# 7688A-kit-V2-2.net
KiCad netlist of a schematic drawn in Altium Designer
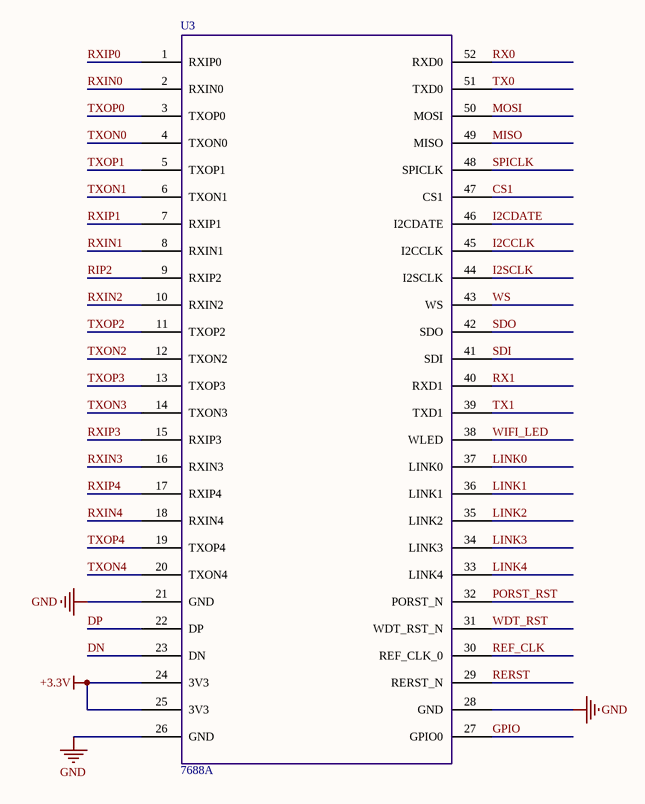
[diagram p0: 7688A-kit-V2-2.SchDoc]

(export (version "E")
  (design (tool "Eeschema 10.0.6"))
  (components
    (comp (ref "U3")
      (value "7688A")
      (footprint "7688A:RM08K_52pin")
      (libsource (lib "7688A") (part "Component_1"))
    )
  )
  (nets
    (net (code "1") (name "+3.3V") (class "Default")
      (node (ref "U3") (pin "24") (pinfunction "3V3_24") (pintype "passive"))
      (node (ref "U3") (pin "25") (pinfunction "3V3_25") (pintype "passive"))
    )
    (net (code "2") (name "/CS1") (class "Default")
      (node (ref "U3") (pin "47") (pinfunction "CS1_47") (pintype "passive"))
    )
    (net (code "3") (name "/DN") (class "Default")
      (node (ref "U3") (pin "23") (pinfunction "DN_23") (pintype "passive"))
    )
    (net (code "4") (name "/DP") (class "Default")
      (node (ref "U3") (pin "22") (pinfunction "DP_22") (pintype "passive"))
    )
    (net (code "5") (name "/GPIO") (class "Default")
      (node (ref "U3") (pin "27") (pinfunction "GPIO0_27") (pintype "passive"))
    )
    (net (code "6") (name "/I2CCLK") (class "Default")
      (node (ref "U3") (pin "45") (pinfunction "I2CCLK_45") (pintype "passive"))
    )
    (net (code "7") (name "/I2CDATE") (class "Default")
      (node (ref "U3") (pin "46") (pinfunction "I2CDATE_46") (pintype "passive"))
    )
    (net (code "8") (name "/I2SCLK") (class "Default")
      (node (ref "U3") (pin "44") (pinfunction "I2SCLK_44") (pintype "passive"))
    )
    (net (code "9") (name "/LINK0") (class "Default")
      (node (ref "U3") (pin "37") (pinfunction "LINK0_37") (pintype "passive"))
    )
    (net (code "10") (name "/LINK1") (class "Default")
      (node (ref "U3") (pin "36") (pinfunction "LINK1_36") (pintype "passive"))
    )
    (net (code "11") (name "/LINK2") (class "Default")
      (node (ref "U3") (pin "35") (pinfunction "LINK2_35") (pintype "passive"))
    )
    (net (code "12") (name "/LINK3") (class "Default")
      (node (ref "U3") (pin "34") (pinfunction "LINK3_34") (pintype "passive"))
    )
    (net (code "13") (name "/LINK4") (class "Default")
      (node (ref "U3") (pin "33") (pinfunction "LINK4_33") (pintype "passive"))
    )
    (net (code "14") (name "/MISO") (class "Default")
      (node (ref "U3") (pin "49") (pinfunction "MISO_49") (pintype "passive"))
    )
    (net (code "15") (name "/MOSI") (class "Default")
      (node (ref "U3") (pin "50") (pinfunction "MOSI_50") (pintype "passive"))
    )
    (net (code "16") (name "/PORST_RST") (class "Default")
      (node (ref "U3") (pin "32") (pinfunction "PORST_N_32") (pintype "passive"))
    )
    (net (code "17") (name "/REF_CLK") (class "Default")
      (node (ref "U3") (pin "30") (pinfunction "REF_CLK_0_30") (pintype "passive"))
    )
    (net (code "18") (name "/RERST") (class "Default")
      (node (ref "U3") (pin "29") (pinfunction "RERST_N_29") (pintype "passive"))
    )
    (net (code "19") (name "/RIP2") (class "Default")
      (node (ref "U3") (pin "9") (pinfunction "RXIP2_9") (pintype "passive"))
    )
    (net (code "20") (name "/RX0") (class "Default")
      (node (ref "U3") (pin "52") (pinfunction "RXD0_52") (pintype "passive"))
    )
    (net (code "21") (name "/RX1") (class "Default")
      (node (ref "U3") (pin "40") (pinfunction "RXD1_40") (pintype "passive"))
    )
    (net (code "22") (name "/RXIN0") (class "Default")
      (node (ref "U3") (pin "2") (pinfunction "RXIN0_2") (pintype "passive"))
    )
    (net (code "23") (name "/RXIN1") (class "Default")
      (node (ref "U3") (pin "8") (pinfunction "RXIN1_8") (pintype "passive"))
    )
    (net (code "24") (name "/RXIN2") (class "Default")
      (node (ref "U3") (pin "10") (pinfunction "RXIN2_10") (pintype "passive"))
    )
    (net (code "25") (name "/RXIN3") (class "Default")
      (node (ref "U3") (pin "16") (pinfunction "RXIN3_16") (pintype "passive"))
    )
    (net (code "26") (name "/RXIN4") (class "Default")
      (node (ref "U3") (pin "18") (pinfunction "RXIN4_18") (pintype "passive"))
    )
    (net (code "27") (name "/RXIP0") (class "Default")
      (node (ref "U3") (pin "1") (pinfunction "RXIP0_1") (pintype "passive"))
    )
    (net (code "28") (name "/RXIP1") (class "Default")
      (node (ref "U3") (pin "7") (pinfunction "RXIP1_7") (pintype "passive"))
    )
    (net (code "29") (name "/RXIP3") (class "Default")
      (node (ref "U3") (pin "15") (pinfunction "RXIP3_15") (pintype "passive"))
    )
    (net (code "30") (name "/RXIP4") (class "Default")
      (node (ref "U3") (pin "17") (pinfunction "RXIP4_17") (pintype "passive"))
    )
    (net (code "31") (name "/SDI") (class "Default")
      (node (ref "U3") (pin "41") (pinfunction "SDI_41") (pintype "passive"))
    )
    (net (code "32") (name "/SDO") (class "Default")
      (node (ref "U3") (pin "42") (pinfunction "SDO_42") (pintype "passive"))
    )
    (net (code "33") (name "/SPICLK") (class "Default")
      (node (ref "U3") (pin "48") (pinfunction "SPICLK_48") (pintype "passive"))
    )
    (net (code "34") (name "/TX0") (class "Default")
      (node (ref "U3") (pin "51") (pinfunction "TXD0_51") (pintype "passive"))
    )
    (net (code "35") (name "/TX1") (class "Default")
      (node (ref "U3") (pin "39") (pinfunction "TXD1_39") (pintype "passive"))
    )
    (net (code "36") (name "/TXON0") (class "Default")
      (node (ref "U3") (pin "4") (pinfunction "TXON0_4") (pintype "passive"))
    )
    (net (code "37") (name "/TXON1") (class "Default")
      (node (ref "U3") (pin "6") (pinfunction "TXON1_6") (pintype "passive"))
    )
    (net (code "38") (name "/TXON2") (class "Default")
      (node (ref "U3") (pin "12") (pinfunction "TXON2_12") (pintype "passive"))
    )
    (net (code "39") (name "/TXON3") (class "Default")
      (node (ref "U3") (pin "14") (pinfunction "TXON3_14") (pintype "passive"))
    )
    (net (code "40") (name "/TXON4") (class "Default")
      (node (ref "U3") (pin "20") (pinfunction "TXON4_20") (pintype "passive"))
    )
    (net (code "41") (name "/TXOP0") (class "Default")
      (node (ref "U3") (pin "3") (pinfunction "TXOP0_3") (pintype "passive"))
    )
    (net (code "42") (name "/TXOP1") (class "Default")
      (node (ref "U3") (pin "5") (pinfunction "TXOP1_5") (pintype "passive"))
    )
    (net (code "43") (name "/TXOP2") (class "Default")
      (node (ref "U3") (pin "11") (pinfunction "TXOP2_11") (pintype "passive"))
    )
    (net (code "44") (name "/TXOP3") (class "Default")
      (node (ref "U3") (pin "13") (pinfunction "TXOP3_13") (pintype "passive"))
    )
    (net (code "45") (name "/TXOP4") (class "Default")
      (node (ref "U3") (pin "19") (pinfunction "TXOP4_19") (pintype "passive"))
    )
    (net (code "46") (name "/WDT_RST") (class "Default")
      (node (ref "U3") (pin "31") (pinfunction "WDT_RST_N_31") (pintype "passive"))
    )
    (net (code "47") (name "/WIFI_LED") (class "Default")
      (node (ref "U3") (pin "38") (pinfunction "WLED_38") (pintype "passive"))
    )
    (net (code "48") (name "/WS") (class "Default")
      (node (ref "U3") (pin "43") (pinfunction "WS_43") (pintype "passive"))
    )
    (net (code "49") (name "GND") (class "Default")
      (node (ref "U3") (pin "21") (pinfunction "GND_21") (pintype "passive"))
      (node (ref "U3") (pin "26") (pinfunction "GND_26") (pintype "passive"))
      (node (ref "U3") (pin "28") (pinfunction "GND_28") (pintype "passive"))
    )
  )
)
